# TinyG-Shield-for-Due.net
KiCad netlist of a schematic drawn in EAGLE
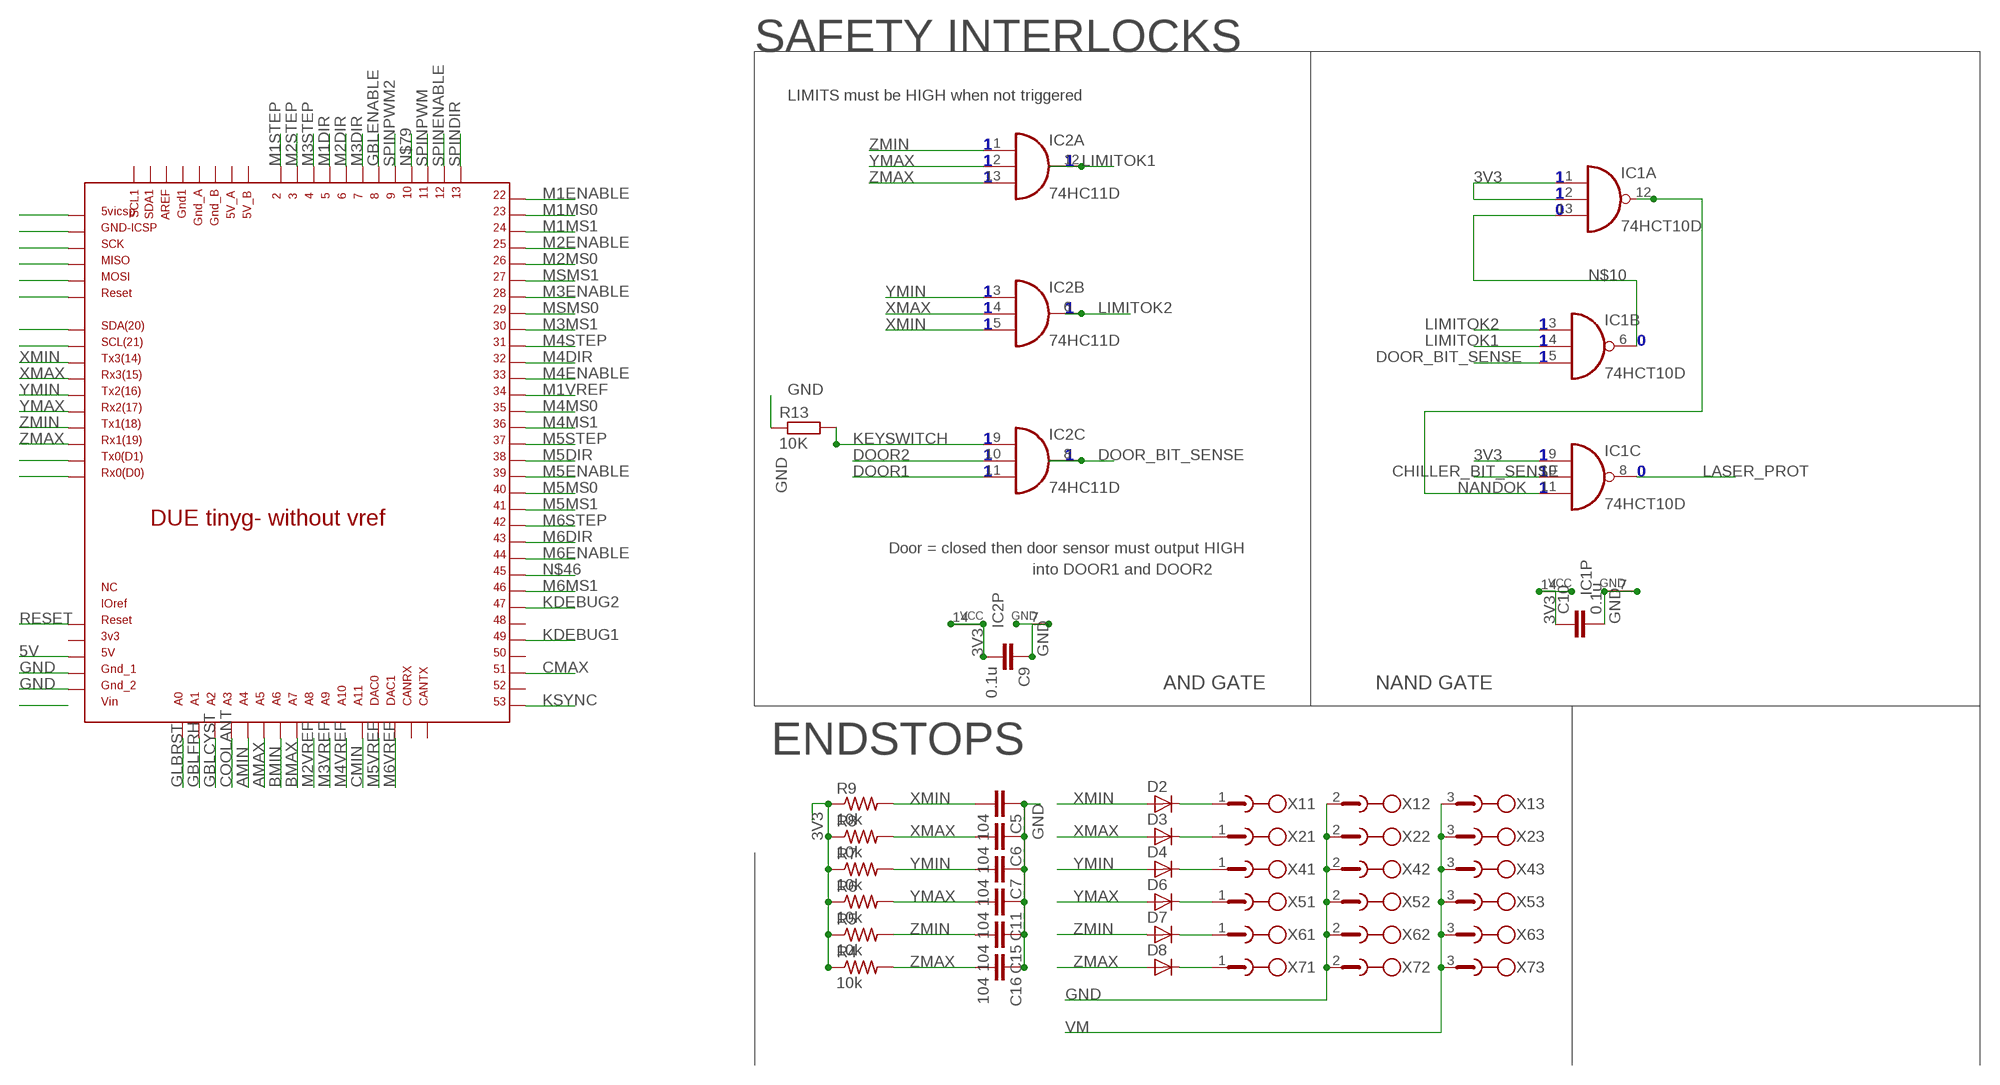
[diagram p0: schematic, sheet 1]
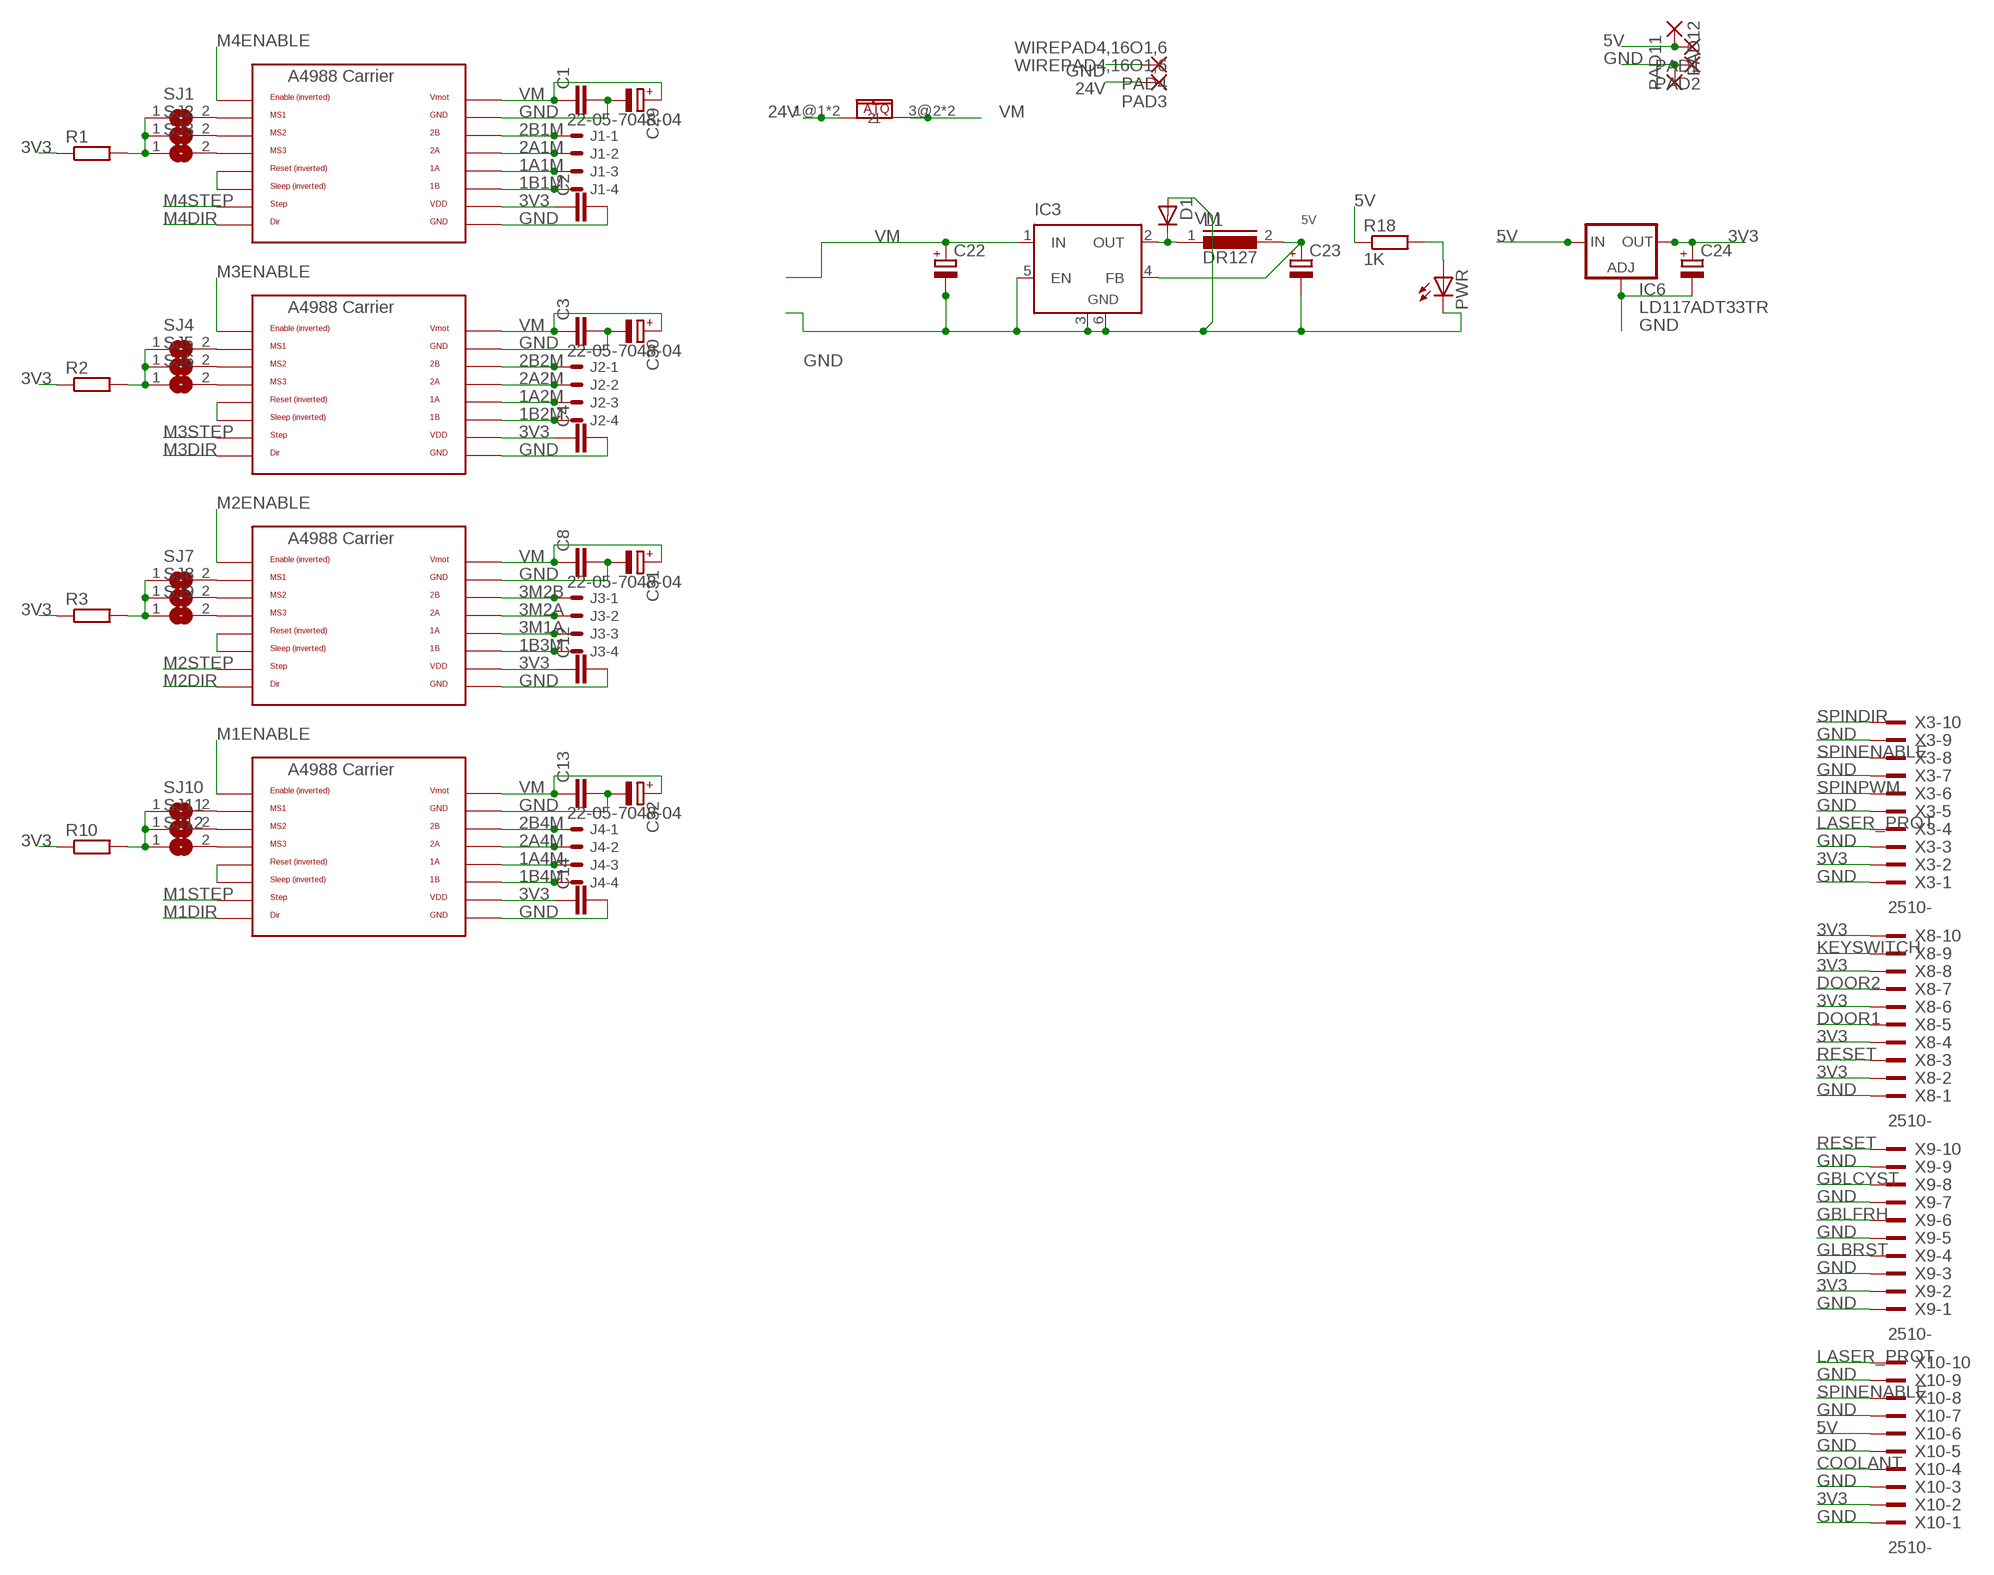
[diagram p1: schematic, sheet 2]

(export (version "E")
  (design (tool "Eeschema 10.0.6"))
  (components
    (comp (ref "C5")
      (value "104")
      (footprint "eagle-import:C1206")
      (libsource (lib "eagle-import") (part "C-EUC1206"))
    )
    (comp (ref "C6")
      (value "104")
      (footprint "eagle-import:C1206")
      (libsource (lib "eagle-import") (part "C-EUC1206"))
    )
    (comp (ref "C7")
      (value "104")
      (footprint "eagle-import:C1206")
      (libsource (lib "eagle-import") (part "C-EUC1206"))
    )
    (comp (ref "C9")
      (value "0.1u")
      (footprint "eagle-import:1206")
      (libsource (lib "eagle-import") (part "CAP1206"))
    )
    (comp (ref "C10")
      (value "0.1u")
      (footprint "eagle-import:1206")
      (libsource (lib "eagle-import") (part "CAP1206"))
    )
    (comp (ref "C11")
      (value "104")
      (footprint "eagle-import:C1206")
      (libsource (lib "eagle-import") (part "C-EUC1206"))
    )
    (comp (ref "C15")
      (value "104")
      (footprint "eagle-import:C1206")
      (libsource (lib "eagle-import") (part "C-EUC1206"))
    )
    (comp (ref "C16")
      (value "104")
      (footprint "eagle-import:C1206")
      (libsource (lib "eagle-import") (part "C-EUC1206"))
    )
    (comp (ref "D2")
      (value "D-SOD-87")
      (footprint "eagle-import:SOD87")
      (libsource (lib "eagle-import") (part "D-SOD-87"))
    )
    (comp (ref "D3")
      (value "D-SOD-87")
      (footprint "eagle-import:SOD87")
      (libsource (lib "eagle-import") (part "D-SOD-87"))
    )
    (comp (ref "D4")
      (value "D-SOD-87")
      (footprint "eagle-import:SOD87")
      (libsource (lib "eagle-import") (part "D-SOD-87"))
    )
    (comp (ref "D6")
      (value "D-SOD-87")
      (footprint "eagle-import:SOD87")
      (libsource (lib "eagle-import") (part "D-SOD-87"))
    )
    (comp (ref "D7")
      (value "D-SOD-87")
      (footprint "eagle-import:SOD87")
      (libsource (lib "eagle-import") (part "D-SOD-87"))
    )
    (comp (ref "D8")
      (value "D-SOD-87")
      (footprint "eagle-import:SOD87")
      (libsource (lib "eagle-import") (part "D-SOD-87"))
    )
    (comp (ref "IC1")
      (value "74HCT10D")
      (footprint "eagle-import:SO14")
      (libsource (lib "eagle-import") (part "7410DHCT"))
    )
    (comp (ref "IC2")
      (value "74HC11D")
      (footprint "eagle-import:SO14")
      (libsource (lib "eagle-import") (part "7411DHC"))
    )
    (comp (ref "R4")
      (value "10k")
      (footprint "eagle-import:M1206")
      (libsource (lib "eagle-import") (part "R-US_M1206"))
    )
    (comp (ref "R5")
      (value "10k")
      (footprint "eagle-import:M1206")
      (libsource (lib "eagle-import") (part "R-US_M1206"))
    )
    (comp (ref "R6")
      (value "10k")
      (footprint "eagle-import:M1206")
      (libsource (lib "eagle-import") (part "R-US_M1206"))
    )
    (comp (ref "R7")
      (value "10k")
      (footprint "eagle-import:M1206")
      (libsource (lib "eagle-import") (part "R-US_M1206"))
    )
    (comp (ref "R8")
      (value "10k")
      (footprint "eagle-import:M1206")
      (libsource (lib "eagle-import") (part "R-US_M1206"))
    )
    (comp (ref "R9")
      (value "10k")
      (footprint "eagle-import:M1206")
      (libsource (lib "eagle-import") (part "R-US_M1206"))
    )
    (comp (ref "R13")
      (value "10K")
      (footprint "eagle-import:M1206")
      (libsource (lib "eagle-import") (part "resistor_R-EU_M1206"))
    )
    (comp (ref "U$1")
      (value "DUE3-TINYG")
      (footprint "eagle-import:DUE-TINYG")
      (libsource (lib "eagle-import") (part "DUE3-TINYG"))
    )
    (comp (ref "X1")
      (value "MC1.5/3")
      (footprint "eagle-import:MC1.5_3-G-3.81")
      (libsource (lib "eagle-import") (part "MC1.5/3"))
    )
    (comp (ref "X2")
      (value "MC1.5/3")
      (footprint "eagle-import:MC1.5_3-G-3.81")
      (libsource (lib "eagle-import") (part "MC1.5/3"))
    )
    (comp (ref "X4")
      (value "MC1.5/3")
      (footprint "eagle-import:MC1.5_3-G-3.81")
      (libsource (lib "eagle-import") (part "MC1.5/3"))
    )
    (comp (ref "X5")
      (value "MC1.5/3")
      (footprint "eagle-import:MC1.5_3-G-3.81")
      (libsource (lib "eagle-import") (part "MC1.5/3"))
    )
    (comp (ref "X6")
      (value "MC1.5/3")
      (footprint "eagle-import:MC1.5_3-G-3.81")
      (libsource (lib "eagle-import") (part "MC1.5/3"))
    )
    (comp (ref "X7")
      (value "MC1.5/3")
      (footprint "eagle-import:MC1.5_3-G-3.81")
      (libsource (lib "eagle-import") (part "MC1.5/3"))
    )
    (comp (ref "C1")
      (value "C-EUC1206")
      (footprint "eagle-import:C1206")
      (libsource (lib "eagle-import") (part "C-EUC1206"))
    )
    (comp (ref "C2")
      (value "C-EUC1206")
      (footprint "eagle-import:C1206")
      (libsource (lib "eagle-import") (part "C-EUC1206"))
    )
    (comp (ref "C3")
      (value "C-EUC1206")
      (footprint "eagle-import:C1206")
      (libsource (lib "eagle-import") (part "C-EUC1206"))
    )
    (comp (ref "C4")
      (value "C-EUC1206")
      (footprint "eagle-import:C1206")
      (libsource (lib "eagle-import") (part "C-EUC1206"))
    )
    (comp (ref "C8")
      (value "C-EUC1206")
      (footprint "eagle-import:C1206")
      (libsource (lib "eagle-import") (part "C-EUC1206"))
    )
    (comp (ref "C12")
      (value "C-EUC1206")
      (footprint "eagle-import:C1206")
      (libsource (lib "eagle-import") (part "C-EUC1206"))
    )
    (comp (ref "C13")
      (value "C-EUC1206")
      (footprint "eagle-import:C1206")
      (libsource (lib "eagle-import") (part "C-EUC1206"))
    )
    (comp (ref "C14")
      (value "C-EUC1206")
      (footprint "eagle-import:C1206")
      (libsource (lib "eagle-import") (part "C-EUC1206"))
    )
    (comp (ref "C22")
      (value "CPOL-EUE")
      (footprint "eagle-import:PANASONIC_E")
      (libsource (lib "eagle-import") (part "resistor_CPOL-EUE"))
    )
    (comp (ref "C23")
      (value "CPOL-EUE")
      (footprint "eagle-import:PANASONIC_E")
      (libsource (lib "eagle-import") (part "resistor_CPOL-EUE"))
    )
    (comp (ref "C24")
      (value "CPOL-EUD")
      (footprint "eagle-import:PANASONIC_D")
      (libsource (lib "eagle-import") (part "CPOL-EUD"))
    )
    (comp (ref "C29")
      (value "CPOL-EUE2,5-6E")
      (footprint "eagle-import:E2,5-6E")
      (libsource (lib "eagle-import") (part "CPOL-EUE2,5-6E"))
    )
    (comp (ref "C30")
      (value "CPOL-EUE2,5-6E")
      (footprint "eagle-import:E2,5-6E")
      (libsource (lib "eagle-import") (part "CPOL-EUE2,5-6E"))
    )
    (comp (ref "C31")
      (value "CPOL-EUE2,5-6E")
      (footprint "eagle-import:E2,5-6E")
      (libsource (lib "eagle-import") (part "CPOL-EUE2,5-6E"))
    )
    (comp (ref "C32")
      (value "CPOL-EUE2,5-6E")
      (footprint "eagle-import:E2,5-6E")
      (libsource (lib "eagle-import") (part "CPOL-EUE2,5-6E"))
    )
    (comp (ref "D1")
      (value "D-SOD-87")
      (footprint "eagle-import:SOD87")
      (libsource (lib "eagle-import") (part "D-SOD-87"))
    )
    (comp (ref "IC3")
      (value "LM2596S")
      (footprint "eagle-import:TO263-5")
      (libsource (lib "eagle-import") (part "LM2596S"))
    )
    (comp (ref "IC6")
      (value "LD117ADT33TR")
      (footprint "eagle-import:DPACK")
      (libsource (lib "eagle-import") (part "LD117A?DT33TR"))
    )
    (comp (ref "J1")
      (value "22-05-7048-04")
      (footprint "eagle-import:7395-04")
      (libsource (lib "eagle-import") (part "22-?-0405-7048"))
    )
    (comp (ref "J2")
      (value "22-05-7048-04")
      (footprint "eagle-import:7395-04")
      (libsource (lib "eagle-import") (part "22-?-0405-7048"))
    )
    (comp (ref "J3")
      (value "22-05-7048-04")
      (footprint "eagle-import:7395-04")
      (libsource (lib "eagle-import") (part "22-?-0405-7048"))
    )
    (comp (ref "J4")
      (value "22-05-7048-04")
      (footprint "eagle-import:7395-04")
      (libsource (lib "eagle-import") (part "22-?-0405-7048"))
    )
    (comp (ref "L1")
      (value "DR127")
      (footprint "eagle-import:DR127")
      (libsource (lib "eagle-import") (part "DR127"))
    )
    (comp (ref "PAD1")
      (value "3,81/1,4")
      (footprint "eagle-import:3,81_1,4")
      (libsource (lib "eagle-import") (part "3,81/1,4"))
    )
    (comp (ref "PAD2")
      (value "3,81/1,4")
      (footprint "eagle-import:3,81_1,4")
      (libsource (lib "eagle-import") (part "3,81/1,4"))
    )
    (comp (ref "PAD3")
      (value "WIREPAD4,16O1,6")
      (footprint "eagle-import:4,16O1,6")
      (libsource (lib "eagle-import") (part "WIREPAD4,16O1,6"))
    )
    (comp (ref "PAD4")
      (value "WIREPAD4,16O1,6")
      (footprint "eagle-import:4,16O1,6")
      (libsource (lib "eagle-import") (part "WIREPAD4,16O1,6"))
    )
    (comp (ref "PAD11")
      (value "3,81/1,4")
      (footprint "eagle-import:3,81_1,4")
      (libsource (lib "eagle-import") (part "3,81/1,4"))
    )
    (comp (ref "PAD12")
      (value "3,81/1,4")
      (footprint "eagle-import:3,81_1,4")
      (libsource (lib "eagle-import") (part "3,81/1,4"))
    )
    (comp (ref "PWR")
      (value "LEDCHIPLED_1206")
      (footprint "eagle-import:CHIPLED_1206")
      (libsource (lib "eagle-import") (part "LEDCHIPLED_1206"))
    )
    (comp (ref "R1")
      (value "R-EU_0207/7")
      (footprint "eagle-import:0207_7")
      (libsource (lib "eagle-import") (part "R-EU_0207/7"))
    )
    (comp (ref "R2")
      (value "R-EU_0204/7")
      (footprint "eagle-import:0204_7")
      (libsource (lib "eagle-import") (part "R-EU_0204/7"))
    )
    (comp (ref "R3")
      (value "R-EU_0207/7")
      (footprint "eagle-import:0207_7")
      (libsource (lib "eagle-import") (part "R-EU_0207/7"))
    )
    (comp (ref "R10")
      (value "R-EU_0207/7")
      (footprint "eagle-import:0207_7")
      (libsource (lib "eagle-import") (part "R-EU_0207/7"))
    )
    (comp (ref "R18")
      (value "1K")
      (footprint "eagle-import:M1206")
      (libsource (lib "eagle-import") (part "R-EU_M1206"))
    )
    (comp (ref "SJ1") (value "SJ") (footprint "eagle-import:SJ") (libsource (lib "eagle-import") (part "SJ")))
    (comp (ref "SJ2") (value "SJ") (footprint "eagle-import:SJ") (libsource (lib "eagle-import") (part "SJ")))
    (comp (ref "SJ3") (value "SJ") (footprint "eagle-import:SJ") (libsource (lib "eagle-import") (part "SJ")))
    (comp (ref "SJ4") (value "SJ") (footprint "eagle-import:SJ") (libsource (lib "eagle-import") (part "SJ")))
    (comp (ref "SJ5") (value "SJ") (footprint "eagle-import:SJ") (libsource (lib "eagle-import") (part "SJ")))
    (comp (ref "SJ6") (value "SJ") (footprint "eagle-import:SJ") (libsource (lib "eagle-import") (part "SJ")))
    (comp (ref "SJ7") (value "SJ") (footprint "eagle-import:SJ") (libsource (lib "eagle-import") (part "SJ")))
    (comp (ref "SJ8") (value "SJ") (footprint "eagle-import:SJ") (libsource (lib "eagle-import") (part "SJ")))
    (comp (ref "SJ9") (value "SJ") (footprint "eagle-import:SJ") (libsource (lib "eagle-import") (part "SJ")))
    (comp (ref "SJ10")
      (value "SJ")
      (footprint "eagle-import:SJ")
      (libsource (lib "eagle-import") (part "SJ"))
    )
    (comp (ref "SJ11")
      (value "SJ")
      (footprint "eagle-import:SJ")
      (libsource (lib "eagle-import") (part "SJ"))
    )
    (comp (ref "SJ12")
      (value "SJ")
      (footprint "eagle-import:SJ")
      (libsource (lib "eagle-import") (part "SJ"))
    )
    (comp (ref "U$3")
      (value "POLOLU_A4983CARRIER")
      (footprint "eagle-import:A4988BREAKOUT")
      (libsource (lib "eagle-import") (part "POLOLU_A4983CARRIER"))
    )
    (comp (ref "U$4")
      (value "POLOLU_A4983CARRIER")
      (footprint "eagle-import:A4988BREAKOUT")
      (libsource (lib "eagle-import") (part "POLOLU_A4983CARRIER"))
    )
    (comp (ref "U$5")
      (value "POLOLU_A4983CARRIER")
      (footprint "eagle-import:A4988BREAKOUT")
      (libsource (lib "eagle-import") (part "POLOLU_A4983CARRIER"))
    )
    (comp (ref "U$6")
      (value "POLOLU_A4983CARRIER")
      (footprint "eagle-import:A4988BREAKOUT")
      (libsource (lib "eagle-import") (part "POLOLU_A4983CARRIER"))
    )
    (comp (ref "U$7")
      (value "CQ-121")
      (footprint "eagle-import:CQ121")
      (libsource (lib "eagle-import") (part "CQ-121"))
    )
    (comp (ref "X3")
      (value "2510-")
      (footprint "eagle-import:PAK100_2500-10")
      (fields (field (name "MF") "3M") (field (name "MPN") "2510-6002UB"))
      (libsource (lib "eagle-import") (part "2510-"))
    )
    (comp (ref "X8")
      (value "2510-")
      (footprint "eagle-import:PAK100_2500-10")
      (fields (field (name "MF") "3M") (field (name "MPN") "2510-6002UB"))
      (libsource (lib "eagle-import") (part "2510-"))
    )
    (comp (ref "X9")
      (value "2510-")
      (footprint "eagle-import:PAK100_2500-10")
      (fields (field (name "MF") "3M") (field (name "MPN") "2510-6002UB"))
      (libsource (lib "eagle-import") (part "2510-"))
    )
    (comp (ref "X10")
      (value "2510-")
      (footprint "eagle-import:PAK100_2500-10")
      (fields (field (name "MF") "3M") (field (name "MPN") "2510-6002UB"))
      (libsource (lib "eagle-import") (part "2510-"))
    )
  )
  (nets
    (net (code "1") (name "1A1M") (class "Default")
      (node (ref "J1") (pin "3") (pinfunction "S_3") (pintype "passive"))
      (node (ref "U$3") (pin "1A") (pinfunction "1A_1A") (pintype "output"))
    )
    (net (code "2") (name "1A2M") (class "Default")
      (node (ref "J2") (pin "3") (pinfunction "S_3") (pintype "passive"))
      (node (ref "U$4") (pin "1A") (pinfunction "1A_1A") (pintype "output"))
    )
    (net (code "3") (name "1A4M") (class "Default")
      (node (ref "J4") (pin "3") (pinfunction "S_3") (pintype "passive"))
      (node (ref "U$6") (pin "1A") (pinfunction "1A_1A") (pintype "output"))
    )
    (net (code "4") (name "1B1M") (class "Default")
      (node (ref "J1") (pin "4") (pinfunction "S_4") (pintype "passive"))
      (node (ref "U$3") (pin "1B") (pinfunction "1B_1B") (pintype "output"))
    )
    (net (code "5") (name "1B2M") (class "Default")
      (node (ref "J2") (pin "4") (pinfunction "S_4") (pintype "passive"))
      (node (ref "U$4") (pin "1B") (pinfunction "1B_1B") (pintype "output"))
    )
    (net (code "6") (name "1B3M") (class "Default")
      (node (ref "J3") (pin "4") (pinfunction "S_4") (pintype "passive"))
      (node (ref "U$5") (pin "1B") (pinfunction "1B_1B") (pintype "output"))
    )
    (net (code "7") (name "1B4M") (class "Default")
      (node (ref "J4") (pin "4") (pinfunction "S_4") (pintype "passive"))
      (node (ref "U$6") (pin "1B") (pinfunction "1B_1B") (pintype "output"))
    )
    (net (code "8") (name "2A1M") (class "Default")
      (node (ref "J1") (pin "2") (pinfunction "S_2") (pintype "passive"))
      (node (ref "U$3") (pin "2A") (pinfunction "2A_2A") (pintype "output"))
    )
    (net (code "9") (name "2A2M") (class "Default")
      (node (ref "J2") (pin "2") (pinfunction "S_2") (pintype "passive"))
      (node (ref "U$4") (pin "2A") (pinfunction "2A_2A") (pintype "output"))
    )
    (net (code "10") (name "2A4M") (class "Default")
      (node (ref "J4") (pin "2") (pinfunction "S_2") (pintype "passive"))
      (node (ref "U$6") (pin "2A") (pinfunction "2A_2A") (pintype "output"))
    )
    (net (code "11") (name "2B1M") (class "Default")
      (node (ref "J1") (pin "1") (pinfunction "S_1") (pintype "passive"))
      (node (ref "U$3") (pin "2B") (pinfunction "2B_2B") (pintype "output"))
    )
    (net (code "12") (name "2B2M") (class "Default")
      (node (ref "J2") (pin "1") (pinfunction "S_1") (pintype "passive"))
      (node (ref "U$4") (pin "2B") (pinfunction "2B_2B") (pintype "output"))
    )
    (net (code "13") (name "2B4M") (class "Default")
      (node (ref "J4") (pin "1") (pinfunction "S_1") (pintype "passive"))
      (node (ref "U$6") (pin "2B") (pinfunction "2B_2B") (pintype "output"))
    )
    (net (code "14") (name "3M1A") (class "Default")
      (node (ref "J3") (pin "3") (pinfunction "S_3") (pintype "passive"))
      (node (ref "U$5") (pin "1A") (pinfunction "1A_1A") (pintype "output"))
    )
    (net (code "15") (name "3M2A") (class "Default")
      (node (ref "J3") (pin "2") (pinfunction "S_2") (pintype "passive"))
      (node (ref "U$5") (pin "2A") (pinfunction "2A_2A") (pintype "output"))
    )
    (net (code "16") (name "3M2B") (class "Default")
      (node (ref "J3") (pin "1") (pinfunction "S_1") (pintype "passive"))
      (node (ref "U$5") (pin "2B") (pinfunction "2B_2B") (pintype "output"))
    )
    (net (code "17") (name "3V3") (class "Default")
      (node (ref "C10") (pin "1") (pinfunction "1_1") (pintype "passive"))
      (node (ref "C12") (pin "1") (pinfunction "1_1") (pintype "passive"))
      (node (ref "C14") (pin "1") (pinfunction "1_1") (pintype "passive"))
      (node (ref "C2") (pin "1") (pinfunction "1_1") (pintype "passive"))
      (node (ref "C24") (pin "+") (pinfunction "+_+") (pintype "passive"))
      (node (ref "C4") (pin "1") (pinfunction "1_1") (pintype "passive"))
      (node (ref "C9") (pin "2") (pinfunction "2_2") (pintype "passive"))
      (node (ref "IC1") (pin "1") (pinfunction "I0_1") (pintype "input"))
      (node (ref "IC1") (pin "14") (pinfunction "VCC_14") (pintype "power_in"))
      (node (ref "IC1") (pin "2") (pinfunction "I1_2") (pintype "input"))
      (node (ref "IC1") (pin "9") (pinfunction "I0_9") (pintype "input"))
      (node (ref "IC2") (pin "14") (pinfunction "VCC_14") (pintype "power_in"))
      (node (ref "IC6") (pin "4") (pinfunction "OUT_4") (pintype "passive"))
      (node (ref "R1") (pin "1") (pinfunction "1_1") (pintype "passive"))
      (node (ref "R10") (pin "1") (pinfunction "1_1") (pintype "passive"))
      (node (ref "R2") (pin "1") (pinfunction "1_1") (pintype "passive"))
      (node (ref "R3") (pin "1") (pinfunction "1_1") (pintype "passive"))
      (node (ref "R4") (pin "1") (pinfunction "1_1") (pintype "passive"))
      (node (ref "R5") (pin "1") (pinfunction "1_1") (pintype "passive"))
      (node (ref "R6") (pin "1") (pinfunction "1_1") (pintype "passive"))
      (node (ref "R7") (pin "1") (pinfunction "1_1") (pintype "passive"))
      (node (ref "R8") (pin "1") (pinfunction "1_1") (pintype "passive"))
      (node (ref "R9") (pin "1") (pinfunction "1_1") (pintype "passive"))
      (node (ref "U$3") (pin "VDD") (pinfunction "VDD_VDD") (pintype "power_in"))
      (node (ref "U$4") (pin "VDD") (pinfunction "VDD_VDD") (pintype "power_in"))
      (node (ref "U$5") (pin "VDD") (pinfunction "VDD_VDD") (pintype "power_in"))
      (node (ref "U$6") (pin "VDD") (pinfunction "VDD_VDD") (pintype "power_in"))
      (node (ref "X10") (pin "2") (pinfunction "KL_2") (pintype "passive"))
      (node (ref "X3") (pin "2") (pinfunction "KL_2") (pintype "passive"))
      (node (ref "X8") (pin "10") (pinfunction "KL_10") (pintype "passive"))
      (node (ref "X8") (pin "2") (pinfunction "KL_2") (pintype "passive"))
      (node (ref "X8") (pin "4") (pinfunction "KL_4") (pintype "passive"))
      (node (ref "X8") (pin "6") (pinfunction "KL_6") (pintype "passive"))
      (node (ref "X8") (pin "8") (pinfunction "KL_8") (pintype "passive"))
      (node (ref "X9") (pin "2") (pinfunction "KL_2") (pintype "passive"))
    )
    (net (code "18") (name "5V") (class "Default")
      (node (ref "C23") (pin "+") (pinfunction "+_+") (pintype "passive"))
      (node (ref "IC3") (pin "4") (pinfunction "FB_4") (pintype "input"))
      (node (ref "IC6") (pin "3") (pinfunction "IN_3") (pintype "input"))
      (node (ref "L1") (pin "2") (pinfunction "2_2") (pintype "passive"))
      (node (ref "PAD1") (pin "1") (pinfunction "P_1") (pintype "passive"))
      (node (ref "PAD12") (pin "1") (pinfunction "P_1") (pintype "passive"))
      (node (ref "R18") (pin "1") (pinfunction "1_1") (pintype "passive"))
      (node (ref "U$1") (pin "5V-P") (pinfunction "5V_5V-P") (pintype "bidirectional"))
      (node (ref "X10") (pin "6") (pinfunction "KL_6") (pintype "passive"))
    )
    (net (code "19") (name "24V") (class "Default")
      (node (ref "PAD3") (pin "1") (pinfunction "P_1") (pintype "passive"))
      (node (ref "U$7") (pin "1@1") (pinfunction "1_1@1") (pintype "bidirectional"))
      (node (ref "U$7") (pin "2@1") (pinfunction "1_2@1") (pintype "bidirectional"))
    )
    (net (code "20") (name "AMAX") (class "Default")
      (node (ref "U$1") (pin "A5") (pinfunction "A5_A5") (pintype "bidirectional"))
    )
    (net (code "21") (name "AMIN") (class "Default")
      (node (ref "U$1") (pin "A4") (pinfunction "A4_A4") (pintype "bidirectional"))
    )
    (net (code "22") (name "BMAX") (class "Default")
      (node (ref "U$1") (pin "A7") (pinfunction "A7_A7") (pintype "bidirectional"))
    )
    (net (code "23") (name "BMIN") (class "Default")
      (node (ref "U$1") (pin "A6") (pinfunction "A6_A6") (pintype "bidirectional"))
    )
    (net (code "24") (name "CHILLER_BIT_SENSE") (class "Default")
      (node (ref "IC1") (pin "10") (pinfunction "I1_10") (pintype "input"))
    )
    (net (code "25") (name "CMAX") (class "Default")
      (node (ref "U$1") (pin "51") (pinfunction "51_51") (pintype "bidirectional"))
    )
    (net (code "26") (name "CMIN") (class "Default")
      (node (ref "U$1") (pin "A11") (pinfunction "A11_A11") (pintype "bidirectional"))
    )
    (net (code "27") (name "COOLANT") (class "Default")
      (node (ref "U$1") (pin "A3") (pinfunction "A3_A3") (pintype "bidirectional"))
      (node (ref "X10") (pin "4") (pinfunction "KL_4") (pintype "passive"))
    )
    (net (code "28") (name "DOOR1") (class "Default")
      (node (ref "IC2") (pin "11") (pinfunction "I2_11") (pintype "input"))
      (node (ref "X8") (pin "5") (pinfunction "KL_5") (pintype "passive"))
    )
    (net (code "29") (name "DOOR2") (class "Default")
      (node (ref "IC2") (pin "10") (pinfunction "I1_10") (pintype "input"))
      (node (ref "X8") (pin "7") (pinfunction "KL_7") (pintype "passive"))
    )
    (net (code "30") (name "DOOR_BIT_SENSE") (class "Default")
      (node (ref "IC1") (pin "5") (pinfunction "I2_5") (pintype "input"))
      (node (ref "IC2") (pin "8") (pinfunction "O_8") (pintype "output"))
    )
    (net (code "31") (name "GBLCYST") (class "Default")
      (node (ref "U$1") (pin "A2") (pinfunction "A2_A2") (pintype "bidirectional"))
      (node (ref "X9") (pin "8") (pinfunction "KL_8") (pintype "passive"))
    )
    (net (code "32") (name "GBLENABLE") (class "Default")
      (node (ref "U$1") (pin "8") (pinfunction "8_8") (pintype "bidirectional"))
    )
    (net (code "33") (name "GBLFRH") (class "Default")
      (node (ref "U$1") (pin "A1") (pinfunction "A1_A1") (pintype "bidirectional"))
      (node (ref "X9") (pin "6") (pinfunction "KL_6") (pintype "passive"))
    )
    (net (code "34") (name "GLBRST") (class "Default")
      (node (ref "U$1") (pin "A0") (pinfunction "A0_A0") (pintype "bidirectional"))
      (node (ref "X9") (pin "4") (pinfunction "KL_4") (pintype "passive"))
    )
    (net (code "35") (name "GND") (class "Default")
      (node (ref "C1") (pin "2") (pinfunction "2_2") (pintype "passive"))
      (node (ref "C10") (pin "2") (pinfunction "2_2") (pintype "passive"))
      (node (ref "C11") (pin "1") (pinfunction "1_1") (pintype "passive"))
      (node (ref "C12") (pin "2") (pinfunction "2_2") (pintype "passive"))
      (node (ref "C13") (pin "2") (pinfunction "2_2") (pintype "passive"))
      (node (ref "C14") (pin "2") (pinfunction "2_2") (pintype "passive"))
      (node (ref "C15") (pin "1") (pinfunction "1_1") (pintype "passive"))
      (node (ref "C16") (pin "1") (pinfunction "1_1") (pintype "passive"))
      (node (ref "C2") (pin "2") (pinfunction "2_2") (pintype "passive"))
      (node (ref "C22") (pin "-") (pinfunction "-_-") (pintype "passive"))
      (node (ref "C23") (pin "-") (pinfunction "-_-") (pintype "passive"))
      (node (ref "C24") (pin "-") (pinfunction "-_-") (pintype "passive"))
      (node (ref "C29") (pin "-") (pinfunction "-_-") (pintype "passive"))
      (node (ref "C3") (pin "2") (pinfunction "2_2") (pintype "passive"))
      (node (ref "C30") (pin "-") (pinfunction "-_-") (pintype "passive"))
      (node (ref "C31") (pin "-") (pinfunction "-_-") (pintype "passive"))
      (node (ref "C32") (pin "-") (pinfunction "-_-") (pintype "passive"))
      (node (ref "C4") (pin "2") (pinfunction "2_2") (pintype "passive"))
      (node (ref "C5") (pin "1") (pinfunction "1_1") (pintype "passive"))
      (node (ref "C6") (pin "1") (pinfunction "1_1") (pintype "passive"))
      (node (ref "C7") (pin "1") (pinfunction "1_1") (pintype "passive"))
      (node (ref "C8") (pin "2") (pinfunction "2_2") (pintype "passive"))
      (node (ref "C9") (pin "1") (pinfunction "1_1") (pintype "passive"))
      (node (ref "D1") (pin "2") (pinfunction "A_2") (pintype "passive"))
      (node (ref "IC1") (pin "7") (pinfunction "GND_7") (pintype "power_in"))
      (node (ref "IC2") (pin "7") (pinfunction "GND_7") (pintype "power_in"))
      (node (ref "IC3") (pin "3") (pinfunction "GND_3") (pintype "power_in"))
      (node (ref "IC3") (pin "5") (pinfunction "EN_5") (pintype "input"))
      (node (ref "IC3") (pin "6") (pinfunction "GND_6") (pintype "power_in"))
      (node (ref "IC6") (pin "1") (pinfunction "ADJ_1") (pintype "input"))
      (node (ref "PAD11") (pin "1") (pinfunction "P_1") (pintype "passive"))
      (node (ref "PAD2") (pin "1") (pinfunction "P_1") (pintype "passive"))
      (node (ref "PAD4") (pin "1") (pinfunction "P_1") (pintype "passive"))
      (node (ref "PWR") (pin "C") (pinfunction "C_C") (pintype "passive"))
      (node (ref "R13") (pin "1") (pinfunction "1_1") (pintype "passive"))
      (node (ref "U$1") (pin "GND_1") (pinfunction "GND_1_GND_1") (pintype "bidirectional"))
      (node (ref "U$1") (pin "GND_2") (pinfunction "GND_2_GND_2") (pintype "bidirectional"))
      (node (ref "U$3") (pin "GND") (pinfunction "GND_GND") (pintype "power_in"))
      (node (ref "U$3") (pin "GND@0") (pinfunction "GND_GND@0") (pintype "power_in"))
      (node (ref "U$4") (pin "GND") (pinfunction "GND_GND") (pintype "power_in"))
      (node (ref "U$4") (pin "GND@0") (pinfunction "GND_GND@0") (pintype "power_in"))
      (node (ref "U$5") (pin "GND") (pinfunction "GND_GND") (pintype "power_in"))
      (node (ref "U$5") (pin "GND@0") (pinfunction "GND_GND@0") (pintype "power_in"))
      (node (ref "U$6") (pin "GND") (pinfunction "GND_GND") (pintype "power_in"))
      (node (ref "U$6") (pin "GND@0") (pinfunction "GND_GND@0") (pintype "power_in"))
      (node (ref "X1") (pin "2") (pinfunction "1_2") (pintype "passive"))
      (node (ref "X10") (pin "1") (pinfunction "KL_1") (pintype "passive"))
      (node (ref "X10") (pin "3") (pinfunction "KL_3") (pintype "passive"))
      (node (ref "X10") (pin "5") (pinfunction "KL_5") (pintype "passive"))
      (node (ref "X10") (pin "7") (pinfunction "KL_7") (pintype "passive"))
      (node (ref "X10") (pin "9") (pinfunction "KL_9") (pintype "passive"))
      (node (ref "X2") (pin "2") (pinfunction "1_2") (pintype "passive"))
      (node (ref "X3") (pin "1") (pinfunction "KL_1") (pintype "passive"))
      (node (ref "X3") (pin "3") (pinfunction "KL_3") (pintype "passive"))
      (node (ref "X3") (pin "5") (pinfunction "KL_5") (pintype "passive"))
      (node (ref "X3") (pin "7") (pinfunction "KL_7") (pintype "passive"))
      (node (ref "X3") (pin "9") (pinfunction "KL_9") (pintype "passive"))
      (node (ref "X4") (pin "2") (pinfunction "1_2") (pintype "passive"))
      (node (ref "X5") (pin "2") (pinfunction "1_2") (pintype "passive"))
      (node (ref "X6") (pin "2") (pinfunction "1_2") (pintype "passive"))
      (node (ref "X7") (pin "2") (pinfunction "1_2") (pintype "passive"))
      (node (ref "X8") (pin "1") (pinfunction "KL_1") (pintype "passive"))
      (node (ref "X9") (pin "1") (pinfunction "KL_1") (pintype "passive"))
      (node (ref "X9") (pin "3") (pinfunction "KL_3") (pintype "passive"))
      (node (ref "X9") (pin "5") (pinfunction "KL_5") (pintype "passive"))
      (node (ref "X9") (pin "7") (pinfunction "KL_7") (pintype "passive"))
      (node (ref "X9") (pin "9") (pinfunction "KL_9") (pintype "passive"))
    )
    (net (code "36") (name "KDEBUG1") (class "Default")
      (node (ref "U$1") (pin "49") (pinfunction "49_49") (pintype "bidirectional"))
    )
    (net (code "37") (name "KDEBUG2") (class "Default")
      (node (ref "U$1") (pin "47") (pinfunction "47_47") (pintype "bidirectional"))
    )
    (net (code "38") (name "KEYSWITCH") (class "Default")
      (node (ref "IC2") (pin "9") (pinfunction "I0_9") (pintype "input"))
      (node (ref "R13") (pin "2") (pinfunction "2_2") (pintype "passive"))
      (node (ref "X8") (pin "9") (pinfunction "KL_9") (pintype "passive"))
    )
    (net (code "39") (name "KSYNC") (class "Default")
      (node (ref "U$1") (pin "53") (pinfunction "53_53") (pintype "bidirectional"))
    )
    (net (code "40") (name "LASER_PROT") (class "Default")
      (node (ref "IC1") (pin "8") (pinfunction "O_8") (pintype "output"))
      (node (ref "X10") (pin "10") (pinfunction "KL_10") (pintype "passive"))
      (node (ref "X3") (pin "4") (pinfunction "KL_4") (pintype "passive"))
    )
    (net (code "41") (name "LIMITOK1") (class "Default")
      (node (ref "IC1") (pin "4") (pinfunction "I1_4") (pintype "input"))
      (node (ref "IC2") (pin "12") (pinfunction "O_12") (pintype "output"))
    )
    (net (code "42") (name "LIMITOK2") (class "Default")
      (node (ref "IC1") (pin "3") (pinfunction "I0_3") (pintype "input"))
      (node (ref "IC2") (pin "6") (pinfunction "O_6") (pintype "output"))
    )
    (net (code "43") (name "M1DIR") (class "Default")
      (node (ref "U$1") (pin "5") (pinfunction "5_5") (pintype "bidirectional"))
      (node (ref "U$6") (pin "DIR") (pinfunction "DIR_DIR") (pintype "input"))
    )
    (net (code "44") (name "M1ENABLE") (class "Default")
      (node (ref "U$1") (pin "22") (pinfunction "22_22") (pintype "bidirectional"))
      (node (ref "U$6") (pin "EN") (pinfunction "EN_EN") (pintype "input"))
    )
    (net (code "45") (name "M1MS0") (class "Default")
      (node (ref "U$1") (pin "23") (pinfunction "23_23") (pintype "bidirectional"))
    )
    (net (code "46") (name "M1MS1") (class "Default")
      (node (ref "U$1") (pin "24") (pinfunction "24_24") (pintype "bidirectional"))
    )
    (net (code "47") (name "M1STEP") (class "Default")
      (node (ref "U$1") (pin "2") (pinfunction "2_2") (pintype "bidirectional"))
      (node (ref "U$6") (pin "STEP") (pinfunction "STEP_STEP") (pintype "input"))
    )
    (net (code "48") (name "M1VREF") (class "Default")
      (node (ref "U$1") (pin "34") (pinfunction "34_34") (pintype "bidirectional"))
    )
    (net (code "49") (name "M2DIR") (class "Default")
      (node (ref "U$1") (pin "6") (pinfunction "6_6") (pintype "bidirectional"))
      (node (ref "U$5") (pin "DIR") (pinfunction "DIR_DIR") (pintype "input"))
    )
    (net (code "50") (name "M2ENABLE") (class "Default")
      (node (ref "U$1") (pin "25") (pinfunction "25_25") (pintype "bidirectional"))
      (node (ref "U$5") (pin "EN") (pinfunction "EN_EN") (pintype "input"))
    )
    (net (code "51") (name "M2MS0") (class "Default")
      (node (ref "U$1") (pin "26") (pinfunction "26_26") (pintype "bidirectional"))
    )
    (net (code "52") (name "M2STEP") (class "Default")
      (node (ref "U$1") (pin "3") (pinfunction "3_3") (pintype "bidirectional"))
      (node (ref "U$5") (pin "STEP") (pinfunction "STEP_STEP") (pintype "input"))
    )
    (net (code "54") (name "M3DIR") (class "Default")
      (node (ref "U$1") (pin "7") (pinfunction "7_7") (pintype "bidirectional"))
      (node (ref "U$4") (pin "DIR") (pinfunction "DIR_DIR") (pintype "input"))
    )
    (net (code "55") (name "M3ENABLE") (class "Default")
      (node (ref "U$1") (pin "28") (pinfunction "28_28") (pintype "bidirectional"))
      (node (ref "U$4") (pin "EN") (pinfunction "EN_EN") (pintype "input"))
    )
    (net (code "56") (name "M3MS1") (class "Default")
      (node (ref "U$1") (pin "30") (pinfunction "30_30") (pintype "bidirectional"))
    )
    (net (code "57") (name "M3STEP") (class "Default")
      (node (ref "U$1") (pin "4") (pinfunction "4_4") (pintype "bidirectional"))
      (node (ref "U$4") (pin "STEP") (pinfunction "STEP_STEP") (pintype "input"))
    )
    (net (code "59") (name "M4DIR") (class "Default")
      (node (ref "U$1") (pin "32") (pinfunction "32_32") (pintype "bidirectional"))
      (node (ref "U$3") (pin "DIR") (pinfunction "DIR_DIR") (pintype "input"))
    )
    (net (code "60") (name "M4ENABLE") (class "Default")
      (node (ref "U$1") (pin "33") (pinfunction "33_33") (pintype "bidirectional"))
      (node (ref "U$3") (pin "EN") (pinfunction "EN_EN") (pintype "input"))
    )
    (net (code "61") (name "M4MS0") (class "Default")
      (node (ref "U$1") (pin "35") (pinfunction "35_35") (pintype "bidirectional"))
    )
    (net (code "62") (name "M4MS1") (class "Default")
      (node (ref "U$1") (pin "36") (pinfunction "36_36") (pintype "bidirectional"))
    )
    (net (code "63") (name "M4STEP") (class "Default")
      (node (ref "U$1") (pin "31") (pinfunction "31_31") (pintype "bidirectional"))
      (node (ref "U$3") (pin "STEP") (pinfunction "STEP_STEP") (pintype "input"))
    )
    (net (code "65") (name "M5DIR") (class "Default")
      (node (ref "U$1") (pin "38") (pinfunction "38_38") (pintype "bidirectional"))
    )
    (net (code "66") (name "M5ENABLE") (class "Default")
      (node (ref "U$1") (pin "39") (pinfunction "39_39") (pintype "bidirectional"))
    )
    (net (code "67") (name "M5MS0") (class "Default")
      (node (ref "U$1") (pin "40") (pinfunction "40_40") (pintype "bidirectional"))
    )
    (net (code "68") (name "M5MS1") (class "Default")
      (node (ref "U$1") (pin "41") (pinfunction "41_41") (pintype "bidirectional"))
    )
    (net (code "69") (name "M5STEP") (class "Default")
      (node (ref "U$1") (pin "37") (pinfunction "37_37") (pintype "bidirectional"))
    )
    (net (code "70") (name "M5VREF") (class "Default")
      (node (ref "U$1") (pin "DAC0") (pinfunction "DAC0_DAC0") (pintype "bidirectional"))
    )
    (net (code "71") (name "M6DIR") (class "Default")
      (node (ref "U$1") (pin "43") (pinfunction "43_43") (pintype "bidirectional"))
    )
    (net (code "72") (name "M6ENABLE") (class "Default")
      (node (ref "U$1") (pin "44") (pinfunction "44_44") (pintype "bidirectional"))
    )
    (net (code "73") (name "M6MS1") (class "Default")
      (node (ref "U$1") (pin "46") (pinfunction "46_46") (pintype "bidirectional"))
    )
    (net (code "74") (name "M6STEP") (class "Default")
      (node (ref "U$1") (pin "42") (pinfunction "42_42") (pintype "bidirectional"))
    )
    (net (code "75") (name "M6VREF") (class "Default")
      (node (ref "U$1") (pin "DAC1") (pinfunction "DAC1_DAC1") (pintype "bidirectional"))
    )
    (net (code "76") (name "MSMS0") (class "Default")
      (node (ref "U$1") (pin "29") (pinfunction "29_29") (pintype "bidirectional"))
    )
    (net (code "77") (name "MSMS1") (class "Default")
      (node (ref "U$1") (pin "27") (pinfunction "27_27") (pintype "bidirectional"))
    )
    (net (code "78") (name "N$10") (class "Default")
      (node (ref "IC1") (pin "13") (pinfunction "I2_13") (pintype "input"))
      (node (ref "IC1") (pin "6") (pinfunction "O_6") (pintype "output"))
    )
    (net (code "79") (name "N$46") (class "Default")
      (node (ref "U$1") (pin "45") (pinfunction "45_45") (pintype "bidirectional"))
    )
    (net (code "80") (name "N$79") (class "Default")
      (node (ref "U$1") (pin "10") (pinfunction "10_10") (pintype "bidirectional"))
    )
    (net (code "81") (name "NANDOK") (class "Default")
      (node (ref "IC1") (pin "11") (pinfunction "I2_11") (pintype "input"))
      (node (ref "IC1") (pin "12") (pinfunction "O_12") (pintype "output"))
    )
    (net (code "82") (name "Net-(D1-C)") (class "Default")
      (node (ref "D1") (pin "1") (pinfunction "C_1") (pintype "passive"))
      (node (ref "IC3") (pin "2") (pinfunction "OUT_2") (pintype "output"))
      (node (ref "L1") (pin "1") (pinfunction "1_1") (pintype "passive"))
    )
    (net (code "83") (name "Net-(D2-C)") (class "Default")
      (node (ref "D2") (pin "1") (pinfunction "C_1") (pintype "passive"))
      (node (ref "X1") (pin "1") (pinfunction "1_1") (pintype "passive"))
    )
    (net (code "84") (name "Net-(D3-C)") (class "Default")
      (node (ref "D3") (pin "1") (pinfunction "C_1") (pintype "passive"))
      (node (ref "X2") (pin "1") (pinfunction "1_1") (pintype "passive"))
    )
    (net (code "85") (name "Net-(D4-C)") (class "Default")
      (node (ref "D4") (pin "1") (pinfunction "C_1") (pintype "passive"))
      (node (ref "X4") (pin "1") (pinfunction "1_1") (pintype "passive"))
    )
    (net (code "86") (name "Net-(D6-C)") (class "Default")
      (node (ref "D6") (pin "1") (pinfunction "C_1") (pintype "passive"))
      (node (ref "X5") (pin "1") (pinfunction "1_1") (pintype "passive"))
    )
    (net (code "87") (name "Net-(D7-C)") (class "Default")
      (node (ref "D7") (pin "1") (pinfunction "C_1") (pintype "passive"))
      (node (ref "X6") (pin "1") (pinfunction "1_1") (pintype "passive"))
    )
    (net (code "88") (name "Net-(D8-C)") (class "Default")
      (node (ref "D8") (pin "1") (pinfunction "C_1") (pintype "passive"))
      (node (ref "X7") (pin "1") (pinfunction "1_1") (pintype "passive"))
    )
    (net (code "89") (name "Net-(PWR-PadA)") (class "Default")
      (node (ref "PWR") (pin "A") (pinfunction "A_A") (pintype "passive"))
      (node (ref "R18") (pin "2") (pinfunction "2_2") (pintype "passive"))
    )
    (net (code "90") (name "Net-(R1-Pad2)") (class "Default")
      (node (ref "R1") (pin "2") (pinfunction "2_2") (pintype "passive"))
      (node (ref "SJ1") (pin "1") (pinfunction "1_1") (pintype "passive"))
      (node (ref "SJ2") (pin "1") (pinfunction "1_1") (pintype "passive"))
      (node (ref "SJ3") (pin "1") (pinfunction "1_1") (pintype "passive"))
    )
    (net (code "91") (name "Net-(R2-Pad2)") (class "Default")
      (node (ref "R2") (pin "2") (pinfunction "2_2") (pintype "passive"))
      (node (ref "SJ4") (pin "1") (pinfunction "1_1") (pintype "passive"))
      (node (ref "SJ5") (pin "1") (pinfunction "1_1") (pintype "passive"))
      (node (ref "SJ6") (pin "1") (pinfunction "1_1") (pintype "passive"))
    )
    (net (code "92") (name "Net-(R3-Pad2)") (class "Default")
      (node (ref "R3") (pin "2") (pinfunction "2_2") (pintype "passive"))
      (node (ref "SJ7") (pin "1") (pinfunction "1_1") (pintype "passive"))
      (node (ref "SJ8") (pin "1") (pinfunction "1_1") (pintype "passive"))
      (node (ref "SJ9") (pin "1") (pinfunction "1_1") (pintype "passive"))
    )
    (net (code "93") (name "Net-(R10-Pad2)") (class "Default")
      (node (ref "R10") (pin "2") (pinfunction "2_2") (pintype "passive"))
      (node (ref "SJ10") (pin "1") (pinfunction "1_1") (pintype "passive"))
      (node (ref "SJ11") (pin "1") (pinfunction "1_1") (pintype "passive"))
      (node (ref "SJ12") (pin "1") (pinfunction "1_1") (pintype "passive"))
    )
    (net (code "94") (name "Net-(SJ1-Pad2)") (class "Default")
      (node (ref "SJ1") (pin "2") (pinfunction "2_2") (pintype "passive"))
      (node (ref "U$3") (pin "MS1") (pinfunction "MS1_MS1") (pintype "input"))
    )
    (net (code "95") (name "Net-(SJ2-Pad2)") (class "Default")
      (node (ref "SJ2") (pin "2") (pinfunction "2_2") (pintype "passive"))
      (node (ref "U$3") (pin "MS2") (pinfunction "MS2_MS2") (pintype "input"))
    )
    (net (code "96") (name "Net-(SJ3-Pad2)") (class "Default")
      (node (ref "SJ3") (pin "2") (pinfunction "2_2") (pintype "passive"))
      (node (ref "U$3") (pin "MS3") (pinfunction "MS3_MS3") (pintype "input"))
    )
    (net (code "97") (name "Net-(SJ4-Pad2)") (class "Default")
      (node (ref "SJ4") (pin "2") (pinfunction "2_2") (pintype "passive"))
      (node (ref "U$4") (pin "MS1") (pinfunction "MS1_MS1") (pintype "input"))
    )
    (net (code "98") (name "Net-(SJ5-Pad2)") (class "Default")
      (node (ref "SJ5") (pin "2") (pinfunction "2_2") (pintype "passive"))
      (node (ref "U$4") (pin "MS2") (pinfunction "MS2_MS2") (pintype "input"))
    )
    (net (code "99") (name "Net-(SJ6-Pad2)") (class "Default")
      (node (ref "SJ6") (pin "2") (pinfunction "2_2") (pintype "passive"))
      (node (ref "U$4") (pin "MS3") (pinfunction "MS3_MS3") (pintype "input"))
    )
    (net (code "100") (name "Net-(SJ7-Pad2)") (class "Default")
      (node (ref "SJ7") (pin "2") (pinfunction "2_2") (pintype "passive"))
      (node (ref "U$5") (pin "MS1") (pinfunction "MS1_MS1") (pintype "input"))
    )
    (net (code "101") (name "Net-(SJ8-Pad2)") (class "Default")
      (node (ref "SJ8") (pin "2") (pinfunction "2_2") (pintype "passive"))
      (node (ref "U$5") (pin "MS2") (pinfunction "MS2_MS2") (pintype "input"))
    )
    (net (code "102") (name "Net-(SJ9-Pad2)") (class "Default")
      (node (ref "SJ9") (pin "2") (pinfunction "2_2") (pintype "passive"))
      (node (ref "U$5") (pin "MS3") (pinfunction "MS3_MS3") (pintype "input"))
    )
    (net (code "103") (name "Net-(SJ10-Pad2)") (class "Default")
      (node (ref "SJ10") (pin "2") (pinfunction "2_2") (pintype "passive"))
      (node (ref "U$6") (pin "MS1") (pinfunction "MS1_MS1") (pintype "input"))
    )
    (net (code "104") (name "Net-(SJ11-Pad2)") (class "Default")
      (node (ref "SJ11") (pin "2") (pinfunction "2_2") (pintype "passive"))
      (node (ref "U$6") (pin "MS2") (pinfunction "MS2_MS2") (pintype "input"))
    )
    (net (code "105") (name "Net-(SJ12-Pad2)") (class "Default")
      (node (ref "SJ12") (pin "2") (pinfunction "2_2") (pintype "passive"))
      (node (ref "U$6") (pin "MS3") (pinfunction "MS3_MS3") (pintype "input"))
    )
    (net (code "106") (name "Net-(U$3-SLEEP)") (class "Default")
      (node (ref "U$3") (pin "RST") (pinfunction "RST_RST") (pintype "input"))
      (node (ref "U$3") (pin "SLP") (pinfunction "SLEEP_SLP") (pintype "input"))
    )
    (net (code "107") (name "Net-(U$4-SLEEP)") (class "Default")
      (node (ref "U$4") (pin "RST") (pinfunction "RST_RST") (pintype "input"))
      (node (ref "U$4") (pin "SLP") (pinfunction "SLEEP_SLP") (pintype "input"))
    )
    (net (code "108") (name "Net-(U$5-SLEEP)") (class "Default")
      (node (ref "U$5") (pin "RST") (pinfunction "RST_RST") (pintype "input"))
      (node (ref "U$5") (pin "SLP") (pinfunction "SLEEP_SLP") (pintype "input"))
    )
    (net (code "109") (name "Net-(U$6-SLEEP)") (class "Default")
      (node (ref "U$6") (pin "RST") (pinfunction "RST_RST") (pintype "input"))
      (node (ref "U$6") (pin "SLP") (pinfunction "SLEEP_SLP") (pintype "input"))
    )
    (net (code "110") (name "RESET") (class "Default")
      (node (ref "U$1") (pin "RESET") (pinfunction "RESET_RESET") (pintype "bidirectional"))
      (node (ref "X8") (pin "3") (pinfunction "KL_3") (pintype "passive"))
      (node (ref "X9") (pin "10") (pinfunction "KL_10") (pintype "passive"))
    )
    (net (code "111") (name "SPINDIR") (class "Default")
      (node (ref "U$1") (pin "13") (pinfunction "13_13") (pintype "bidirectional"))
      (node (ref "X3") (pin "10") (pinfunction "KL_10") (pintype "passive"))
    )
    (net (code "112") (name "SPINENABLE") (class "Default")
      (node (ref "U$1") (pin "12") (pinfunction "12_12") (pintype "bidirectional"))
      (node (ref "X10") (pin "8") (pinfunction "KL_8") (pintype "passive"))
      (node (ref "X3") (pin "8") (pinfunction "KL_8") (pintype "passive"))
    )
    (net (code "113") (name "SPINPWM") (class "Default")
      (node (ref "U$1") (pin "11") (pinfunction "11_11") (pintype "bidirectional"))
      (node (ref "X3") (pin "6") (pinfunction "KL_6") (pintype "passive"))
    )
    (net (code "114") (name "SPINPWM2") (class "Default")
      (node (ref "U$1") (pin "9") (pinfunction "9_9") (pintype "bidirectional"))
    )
    (net (code "115") (name "VM") (class "Default")
      (node (ref "C1") (pin "1") (pinfunction "1_1") (pintype "passive"))
      (node (ref "C13") (pin "1") (pinfunction "1_1") (pintype "passive"))
      (node (ref "C22") (pin "+") (pinfunction "+_+") (pintype "passive"))
      (node (ref "C29") (pin "+") (pinfunction "+_+") (pintype "passive"))
      (node (ref "C3") (pin "1") (pinfunction "1_1") (pintype "passive"))
      (node (ref "C30") (pin "+") (pinfunction "+_+") (pintype "passive"))
      (node (ref "C31") (pin "+") (pinfunction "+_+") (pintype "passive"))
      (node (ref "C32") (pin "+") (pinfunction "+_+") (pintype "passive"))
      (node (ref "C8") (pin "1") (pinfunction "1_1") (pintype "passive"))
      (node (ref "IC3") (pin "1") (pinfunction "IN_1") (pintype "input"))
      (node (ref "U$3") (pin "VMOT") (pinfunction "VMOT_VMOT") (pintype "power_in"))
      (node (ref "U$4") (pin "VMOT") (pinfunction "VMOT_VMOT") (pintype "power_in"))
      (node (ref "U$5") (pin "VMOT") (pinfunction "VMOT_VMOT") (pintype "power_in"))
      (node (ref "U$6") (pin "VMOT") (pinfunction "VMOT_VMOT") (pintype "power_in"))
      (node (ref "U$7") (pin "3@2") (pinfunction "2_3@2") (pintype "bidirectional"))
      (node (ref "U$7") (pin "4@2") (pinfunction "2_4@2") (pintype "bidirectional"))
      (node (ref "X1") (pin "3") (pinfunction "1_3") (pintype "passive"))
      (node (ref "X2") (pin "3") (pinfunction "1_3") (pintype "passive"))
      (node (ref "X4") (pin "3") (pinfunction "1_3") (pintype "passive"))
      (node (ref "X5") (pin "3") (pinfunction "1_3") (pintype "passive"))
      (node (ref "X6") (pin "3") (pinfunction "1_3") (pintype "passive"))
      (node (ref "X7") (pin "3") (pinfunction "1_3") (pintype "passive"))
    )
    (net (code "116") (name "XMAX") (class "Default")
      (node (ref "C6") (pin "2") (pinfunction "2_2") (pintype "passive"))
      (node (ref "D3") (pin "2") (pinfunction "A_2") (pintype "passive"))
      (node (ref "IC2") (pin "4") (pinfunction "I1_4") (pintype "input"))
      (node (ref "R8") (pin "2") (pinfunction "2_2") (pintype "passive"))
      (node (ref "U$1") (pin "RX3") (pinfunction "RX3_RX3") (pintype "bidirectional"))
    )
    (net (code "117") (name "XMIN") (class "Default")
      (node (ref "C5") (pin "2") (pinfunction "2_2") (pintype "passive"))
      (node (ref "D2") (pin "2") (pinfunction "A_2") (pintype "passive"))
      (node (ref "IC2") (pin "5") (pinfunction "I2_5") (pintype "input"))
      (node (ref "R9") (pin "2") (pinfunction "2_2") (pintype "passive"))
      (node (ref "U$1") (pin "TX3") (pinfunction "TX3_TX3") (pintype "bidirectional"))
    )
    (net (code "118") (name "YMAX") (class "Default")
      (node (ref "C11") (pin "2") (pinfunction "2_2") (pintype "passive"))
      (node (ref "D6") (pin "2") (pinfunction "A_2") (pintype "passive"))
      (node (ref "IC2") (pin "2") (pinfunction "I1_2") (pintype "input"))
      (node (ref "R6") (pin "2") (pinfunction "2_2") (pintype "passive"))
      (node (ref "U$1") (pin "RX2") (pinfunction "RX2_RX2") (pintype "bidirectional"))
    )
    (net (code "119") (name "YMIN") (class "Default")
      (node (ref "C7") (pin "2") (pinfunction "2_2") (pintype "passive"))
      (node (ref "D4") (pin "2") (pinfunction "A_2") (pintype "passive"))
      (node (ref "IC2") (pin "3") (pinfunction "I0_3") (pintype "input"))
      (node (ref "R7") (pin "2") (pinfunction "2_2") (pintype "passive"))
      (node (ref "U$1") (pin "TX2") (pinfunction "TX2_TX2") (pintype "bidirectional"))
    )
    (net (code "120") (name "ZMAX") (class "Default")
      (node (ref "C16") (pin "2") (pinfunction "2_2") (pintype "passive"))
      (node (ref "D8") (pin "2") (pinfunction "A_2") (pintype "passive"))
      (node (ref "IC2") (pin "13") (pinfunction "I2_13") (pintype "input"))
      (node (ref "R4") (pin "2") (pinfunction "2_2") (pintype "passive"))
      (node (ref "U$1") (pin "RX1") (pinfunction "RX1_RX1") (pintype "bidirectional"))
    )
    (net (code "121") (name "ZMIN") (class "Default")
      (node (ref "C15") (pin "2") (pinfunction "2_2") (pintype "passive"))
      (node (ref "D7") (pin "2") (pinfunction "A_2") (pintype "passive"))
      (node (ref "IC2") (pin "1") (pinfunction "I0_1") (pintype "input"))
      (node (ref "R5") (pin "2") (pinfunction "2_2") (pintype "passive"))
      (node (ref "U$1") (pin "TX1") (pinfunction "TX1_TX1") (pintype "bidirectional"))
    )
    (net (code "122") (name "unconnected-(U$1-Pad3V3)") (class "Default")
      (node (ref "U$1") (pin "3V3") (pinfunction "3V3_3V3") (pintype "bidirectional"))
    )
    (net (code "123") (name "unconnected-(U$1-Pad5V_A)") (class "Default")
      (node (ref "U$1") (pin "5V_A") (pinfunction "5V_A_5V_A") (pintype "bidirectional"))
    )
    (net (code "124") (name "unconnected-(U$1-Pad5V_B)") (class "Default")
      (node (ref "U$1") (pin "5V_B") (pinfunction "5V_B_5V_B") (pintype "bidirectional"))
    )
    (net (code "125") (name "unconnected-(U$1-Pad5V_ICSP)") (class "Default")
      (node (ref "U$1") (pin "5V_ICSP") (pinfunction "5V_ICSP_5V_ICSP") (pintype "bidirectional"))
    )
    (net (code "126") (name "unconnected-(U$1-Pad48)") (class "Default")
      (node (ref "U$1") (pin "48") (pinfunction "48_48") (pintype "bidirectional"))
    )
    (net (code "127") (name "unconnected-(U$1-Pad50)") (class "Default")
      (node (ref "U$1") (pin "50") (pinfunction "50_50") (pintype "bidirectional"))
    )
    (net (code "128") (name "unconnected-(U$1-Pad52)") (class "Default")
      (node (ref "U$1") (pin "52") (pinfunction "52_52") (pintype "bidirectional"))
    )
    (net (code "129") (name "unconnected-(U$1-PadAREF)") (class "Default")
      (node (ref "U$1") (pin "AREF") (pinfunction "AREF_AREF") (pintype "bidirectional"))
    )
    (net (code "130") (name "unconnected-(U$1-PadCANRX)") (class "Default")
      (node (ref "U$1") (pin "CANRX") (pinfunction "CANRX_CANRX") (pintype "bidirectional"))
    )
    (net (code "131") (name "unconnected-(U$1-PadCANTX)") (class "Default")
      (node (ref "U$1") (pin "CANTX") (pinfunction "CANTX_CANTX") (pintype "bidirectional"))
    )
    (net (code "132") (name "unconnected-(U$1-PadGND1)") (class "Default")
      (node (ref "U$1") (pin "GND1") (pinfunction "GND1_GND1") (pintype "bidirectional"))
    )
    (net (code "133") (name "unconnected-(U$1-PadGND_A)") (class "Default")
      (node (ref "U$1") (pin "GND_A") (pinfunction "GND_A_GND_A") (pintype "bidirectional"))
    )
    (net (code "134") (name "unconnected-(U$1-PadGND_B)") (class "Default")
      (node (ref "U$1") (pin "GND_B") (pinfunction "GND_B_GND_B") (pintype "bidirectional"))
    )
    (net (code "135") (name "unconnected-(U$1-PadGND_ICSP)") (class "Default")
      (node (ref "U$1") (pin "GND_ICSP") (pinfunction "GND_ICSP_GND_ICSP") (pintype "bidirectional"))
    )
    (net (code "136") (name "unconnected-(U$1-PadMISO_ICSP)") (class "Default")
      (node (ref "U$1") (pin "MISO_ICSP") (pinfunction "MISO_ICSP_MISO_ICSP") (pintype "bidirectional"))
    )
    (net (code "137") (name "unconnected-(U$1-PadMOSI_ICSP)") (class "Default")
      (node (ref "U$1") (pin "MOSI_ICSP") (pinfunction "MOSI_ICSP_MOSI_ICSP") (pintype "bidirectional"))
    )
    (net (code "138") (name "unconnected-(U$1-PadRESET_ICSP)") (class "Default")
      (node (ref "U$1") (pin "RESET_ICSP") (pinfunction "RESET_ICSP_RESET_ICSP") (pintype "bidirectional"))
    )
    (net (code "139") (name "unconnected-(U$1-PadRX0)") (class "Default")
      (node (ref "U$1") (pin "RX0") (pinfunction "RX0_RX0") (pintype "bidirectional"))
    )
    (net (code "140") (name "unconnected-(U$1-PadSCK_ICSP)") (class "Default")
      (node (ref "U$1") (pin "SCK_ICSP") (pinfunction "SCK_ICSP_SCK_ICSP") (pintype "bidirectional"))
    )
    (net (code "141") (name "unconnected-(U$1-PadSCL)") (class "Default")
      (node (ref "U$1") (pin "SCL") (pinfunction "SCL_SCL") (pintype "bidirectional"))
    )
    (net (code "142") (name "unconnected-(U$1-PadSCL1)") (class "Default")
      (node (ref "U$1") (pin "SCL1") (pinfunction "SCL1_SCL1") (pintype "bidirectional"))
    )
    (net (code "143") (name "unconnected-(U$1-PadSDA)") (class "Default")
      (node (ref "U$1") (pin "SDA") (pinfunction "SDA_SDA") (pintype "bidirectional"))
    )
    (net (code "144") (name "unconnected-(U$1-PadSDA1)") (class "Default")
      (node (ref "U$1") (pin "SDA1") (pinfunction "SDA1_SDA1") (pintype "bidirectional"))
    )
    (net (code "145") (name "unconnected-(U$1-PadTX0)") (class "Default")
      (node (ref "U$1") (pin "TX0") (pinfunction "TX0_TX0") (pintype "bidirectional"))
    )
  )
)
